# Mach_nguon_on_ap.net
KiCad netlist of a schematic drawn in Altium Designer
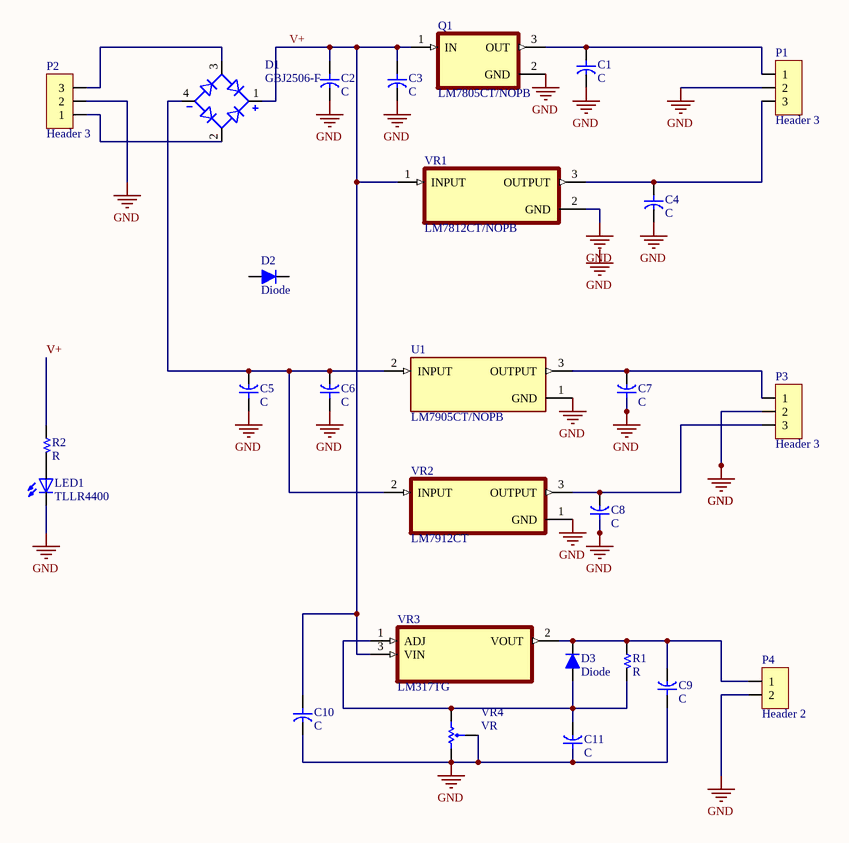
[diagram p0: Mach_nguon_on_ap.SchDoc]

(export (version "E")
  (design (tool "Eeschema 10.0.6"))
  (components
    (comp (ref "C1")
      (value "C")
      (footprint "CYL/D.400/LS.200")
      (description "Capacitor pol")
      (libsource (lib "chipfc_libs") (part "Capacitor"))
    )
    (comp (ref "C2")
      (value "C")
      (footprint "CYL/D.400/LS.200")
      (description "Capacitor pol")
      (libsource (lib "chipfc_libs") (part "Capacitor"))
    )
    (comp (ref "C3")
      (value "C")
      (footprint "CYL/D.400/LS.200")
      (description "Capacitor pol")
      (libsource (lib "chipfc_libs") (part "Capacitor"))
    )
    (comp (ref "C4")
      (value "C")
      (footprint "CYL/D.400/LS.200")
      (description "Capacitor pol")
      (libsource (lib "chipfc_libs") (part "Capacitor"))
    )
    (comp (ref "C5")
      (value "C")
      (footprint "CYL/D.400/LS.200")
      (description "Capacitor pol")
      (libsource (lib "chipfc_libs") (part "Capacitor"))
    )
    (comp (ref "C6")
      (value "C")
      (footprint "CYL/D.400/LS.200")
      (description "Capacitor pol")
      (libsource (lib "chipfc_libs") (part "Capacitor"))
    )
    (comp (ref "C7")
      (value "C")
      (footprint "CYL/D.400/LS.200")
      (description "Capacitor pol")
      (libsource (lib "chipfc_libs") (part "Capacitor"))
    )
    (comp (ref "C8")
      (value "C")
      (footprint "CYL/D.400/LS.200")
      (description "Capacitor pol")
      (libsource (lib "chipfc_libs") (part "Capacitor"))
    )
    (comp (ref "C9")
      (value "C")
      (footprint "CYL/D.400/LS.200")
      (description "Capacitor pol")
      (libsource (lib "chipfc_libs") (part "Capacitor"))
    )
    (comp (ref "C10")
      (value "C")
      (footprint "CYL/D.400/LS.200")
      (description "Capacitor pol")
      (libsource (lib "chipfc_libs") (part "Capacitor"))
    )
    (comp (ref "C11")
      (value "C")
      (footprint "CYL/D.400/LS.200")
      (description "Capacitor pol")
      (libsource (lib "chipfc_libs") (part "Capacitor"))
    )
    (comp (ref "D1")
      (value "GBJ2506-F")
      (footprint "DIOB_GBJ2506-F")
      (description "Bridge Rectifier Single Phase Standard 600 V Through Hole GBJ")
      (fields (field (name "MF") "Diodes Inc."))
      (libsource (lib "GBJ2506-F (1)") (part "GBJ2506-F"))
    )
    (comp (ref "D2")
      (value "Diode")
      (footprint "DO-35 (SOD27 )")
      (description "Default Diode")
      (libsource (lib "chipfc_libs") (part "Diode"))
    )
    (comp (ref "D3")
      (value "Diode")
      (footprint "DO-35 (SOD27 )")
      (description "Default Diode")
      (libsource (lib "chipfc_libs") (part "Diode"))
    )
    (comp (ref "LED1")
      (value "TLLR4400")
      (footprint "LED3MM")
      (description "Red 619nm LED Indication - Discrete 1.9V Radial")
      (fields (field (name "MF") "Vishay"))
      (libsource (lib "TLLR4400") (part "TLLR4400"))
    )
    (comp (ref "P1")
      (value "Header 3")
      (footprint "HDR/Terminal/3")
      (description "Header, 3-Pin")
      (libsource (lib "") (part "Header 3_1"))
    )
    (comp (ref "P2")
      (value "Header 3")
      (footprint "HDR/Terminal/3")
      (description "Header, 3-Pin")
      (libsource (lib "connectors") (part "Header 3"))
    )
    (comp (ref "P3")
      (value "Header 3")
      (footprint "HDR/Terminal/3")
      (description "Header, 3-Pin")
      (libsource (lib "") (part "Header 3_1"))
    )
    (comp (ref "P4")
      (value "Header 2")
      (footprint "HDR/Terminal/2")
      (description "Header, 2-Pin")
      (libsource (lib "connectors") (part "Header 2"))
    )
    (comp (ref "Q1")
      (value "LM7805CT/NOPB")
      (footprint "TO254P1054X470X2600-3")
      (description "Linear Voltage Regulator IC Positive Fixed 1 Output 1.5A TO-220-3")
      (fields (field (name "MF") "ON Semiconductor") (field (name "MP") "LM7805CT"))
      (libsource (lib "LM7805CT_NOPB") (part "LM7805CT/NOPB"))
    )
    (comp (ref "R1")
      (value "R")
      (footprint "R 1/4W/300")
      (description "Resistor")
      (libsource (lib "chipfc_libs") (part "Resistor"))
    )
    (comp (ref "R2")
      (value "R")
      (footprint "R 1/4W/300")
      (description "Resistor")
      (libsource (lib "chipfc_libs") (part "Resistor"))
    )
    (comp (ref "U1")
      (value "LM7905CT/NOPB")
      (footprint "TO254P1016X4575X1955-3")
      (description "1.5-A, negative linear voltage regulator")
      (fields (field (name "MF") "Texas Instruments"))
      (libsource (lib "LM7905CT_NOPB") (part "LM7905CT/NOPB"))
    )
    (comp (ref "VR1")
      (value "LM7812CT/NOPB")
      (footprint "TO254P1054X470X1955-3")
      (description "1.5-A, 30-V, linear voltage regulator")
      (fields (field (name "MF") "Texas Instruments"))
      (libsource (lib "LM7812CT_NOPB") (part "LM7812CT/NOPB"))
    )
    (comp (ref "VR2")
      (value "LM7912CT")
      (footprint "TO254P1054X470X1955-3")
      (description "1.5-A, negative linear voltage regulator 3-TO-220 0 to 125")
      (fields (field (name "MF") "Texas Instruments"))
      (libsource (lib "LM7912CT") (part "LM7912CT"))
    )
    (comp (ref "VR3")
      (value "LM317TG")
      (footprint "TO254P1054X470X1955-3")
      (description "Linear Voltage Regulator IC Positive Adjustable 1 Output 1.5A TO-220-3")
      (fields (field (name "MF") "ON Semiconductor"))
      (libsource (lib "LM317TG") (part "LM317TG"))
    )
    (comp (ref "VR4")
      (value "VR")
      (footprint "R VAR B")
      (description "Resistor Variable")
      (libsource (lib "chipfc_libs") (part "Resistor Variable"))
    )
  )
  (nets
    (net (code "1") (name "/V+") (class "Default")
      (node (ref "C10") (pin "1") (pinfunction "1_1") (pintype "passive"))
      (node (ref "C2") (pin "1") (pinfunction "1_1") (pintype "passive"))
      (node (ref "C3") (pin "1") (pinfunction "1_1") (pintype "passive"))
      (node (ref "D1") (pin "1") (pinfunction "POS_1") (pintype "passive"))
      (node (ref "Q1") (pin "1") (pinfunction "IN_1") (pintype "input"))
      (node (ref "R2") (pin "1") (pinfunction "1_1") (pintype "passive"))
      (node (ref "VR1") (pin "1") (pinfunction "INPUT_1") (pintype "input"))
      (node (ref "VR3") (pin "3") (pinfunction "VIN_3") (pintype "input"))
    )
    (net (code "2") (name "GND") (class "Default")
      (node (ref "C1") (pin "2") (pinfunction "2_2") (pintype "passive"))
      (node (ref "C10") (pin "2") (pinfunction "2_2") (pintype "passive"))
      (node (ref "C11") (pin "1") (pinfunction "1_1") (pintype "passive"))
      (node (ref "C2") (pin "2") (pinfunction "2_2") (pintype "passive"))
      (node (ref "C3") (pin "2") (pinfunction "2_2") (pintype "passive"))
      (node (ref "C4") (pin "2") (pinfunction "2_2") (pintype "passive"))
      (node (ref "C5") (pin "1") (pinfunction "1_1") (pintype "passive"))
      (node (ref "C6") (pin "1") (pinfunction "1_1") (pintype "passive"))
      (node (ref "C7") (pin "1") (pinfunction "1_1") (pintype "passive"))
      (node (ref "C8") (pin "1") (pinfunction "1_1") (pintype "passive"))
      (node (ref "C9") (pin "1") (pinfunction "1_1") (pintype "passive"))
      (node (ref "LED1") (pin "K") (pinfunction "C_K") (pintype "passive"))
      (node (ref "P1") (pin "2") (pinfunction "2_2") (pintype "passive"))
      (node (ref "P2") (pin "2") (pinfunction "2_2") (pintype "passive"))
      (node (ref "P3") (pin "2") (pinfunction "2_2") (pintype "passive"))
      (node (ref "P4") (pin "2") (pinfunction "2_2") (pintype "passive"))
      (node (ref "Q1") (pin "2") (pinfunction "GND_2") (pintype "power_in"))
      (node (ref "U1") (pin "1") (pinfunction "GND_1") (pintype "power_in"))
      (node (ref "VR1") (pin "2") (pinfunction "GND_2") (pintype "power_in"))
      (node (ref "VR2") (pin "1") (pinfunction "GND_1") (pintype "power_in"))
      (node (ref "VR4") (pin "2") (pinfunction "2_2") (pintype "passive"))
      (node (ref "VR4") (pin "3") (pinfunction "3_3") (pintype "passive"))
    )
    (net (code "3") (name "Net-(D1-AC1)") (class "Default")
      (node (ref "D1") (pin "2") (pinfunction "AC1_2") (pintype "passive"))
      (node (ref "P2") (pin "1") (pinfunction "1_1") (pintype "passive"))
    )
    (net (code "4") (name "Net-(D1-AC2)") (class "Default")
      (node (ref "D1") (pin "3") (pinfunction "AC2_3") (pintype "passive"))
      (node (ref "P2") (pin "3") (pinfunction "3_3") (pintype "passive"))
    )
    (net (code "5") (name "Net-(D1-NEG)") (class "Default")
      (node (ref "C5") (pin "2") (pinfunction "2_2") (pintype "passive"))
      (node (ref "C6") (pin "2") (pinfunction "2_2") (pintype "passive"))
      (node (ref "D1") (pin "4") (pinfunction "NEG_4") (pintype "passive"))
      (node (ref "U1") (pin "2") (pinfunction "INPUT_2") (pintype "input"))
      (node (ref "VR2") (pin "2") (pinfunction "INPUT_2") (pintype "input"))
    )
    (net (code "6") (name "Net-(D3-A)") (class "Default")
      (node (ref "C11") (pin "2") (pinfunction "2_2") (pintype "passive"))
      (node (ref "D3") (pin "1") (pinfunction "A_1") (pintype "passive"))
      (node (ref "R1") (pin "2") (pinfunction "2_2") (pintype "passive"))
      (node (ref "VR3") (pin "1") (pinfunction "ADJ_1") (pintype "input"))
      (node (ref "VR4") (pin "1") (pinfunction "1_1") (pintype "passive"))
    )
    (net (code "7") (name "Net-(D3-K)") (class "Default")
      (node (ref "C9") (pin "2") (pinfunction "2_2") (pintype "passive"))
      (node (ref "D3") (pin "2") (pinfunction "K_2") (pintype "passive"))
      (node (ref "P4") (pin "1") (pinfunction "1_1") (pintype "passive"))
      (node (ref "R1") (pin "1") (pinfunction "1_1") (pintype "passive"))
      (node (ref "VR3") (pin "2") (pinfunction "VOUT_2") (pintype "output"))
    )
    (net (code "8") (name "Net-(LED1-PadA)") (class "Default")
      (node (ref "LED1") (pin "A") (pinfunction "A_A") (pintype "passive"))
      (node (ref "R2") (pin "2") (pinfunction "2_2") (pintype "passive"))
    )
    (net (code "9") (name "Net-(Q1-OUT)") (class "Default")
      (node (ref "C1") (pin "1") (pinfunction "1_1") (pintype "passive"))
      (node (ref "P1") (pin "1") (pinfunction "1_1") (pintype "passive"))
      (node (ref "Q1") (pin "3") (pinfunction "OUT_3") (pintype "output"))
    )
    (net (code "10") (name "Net-(U1-OUTPUT)") (class "Default")
      (node (ref "C7") (pin "2") (pinfunction "2_2") (pintype "passive"))
      (node (ref "P3") (pin "1") (pinfunction "1_1") (pintype "passive"))
      (node (ref "U1") (pin "3") (pinfunction "OUTPUT_3") (pintype "output"))
    )
    (net (code "11") (name "Net-(VR1-OUTPUT)") (class "Default")
      (node (ref "C4") (pin "1") (pinfunction "1_1") (pintype "passive"))
      (node (ref "P1") (pin "3") (pinfunction "3_3") (pintype "passive"))
      (node (ref "VR1") (pin "3") (pinfunction "OUTPUT_3") (pintype "output"))
    )
    (net (code "12") (name "Net-(VR2-OUTPUT)") (class "Default")
      (node (ref "C8") (pin "2") (pinfunction "2_2") (pintype "passive"))
      (node (ref "P3") (pin "3") (pinfunction "3_3") (pintype "passive"))
      (node (ref "VR2") (pin "3") (pinfunction "OUTPUT_3") (pintype "output"))
    )
    (net (code "13") (name "unconnected-(D2-A-Pad1)") (class "Default")
      (node (ref "D2") (pin "1") (pinfunction "A_1") (pintype "passive"))
    )
    (net (code "14") (name "unconnected-(D2-K-Pad2)") (class "Default")
      (node (ref "D2") (pin "2") (pinfunction "K_2") (pintype "passive"))
    )
  )
)
